# Power.net
KiCad netlist of a schematic drawn in Altium Designer
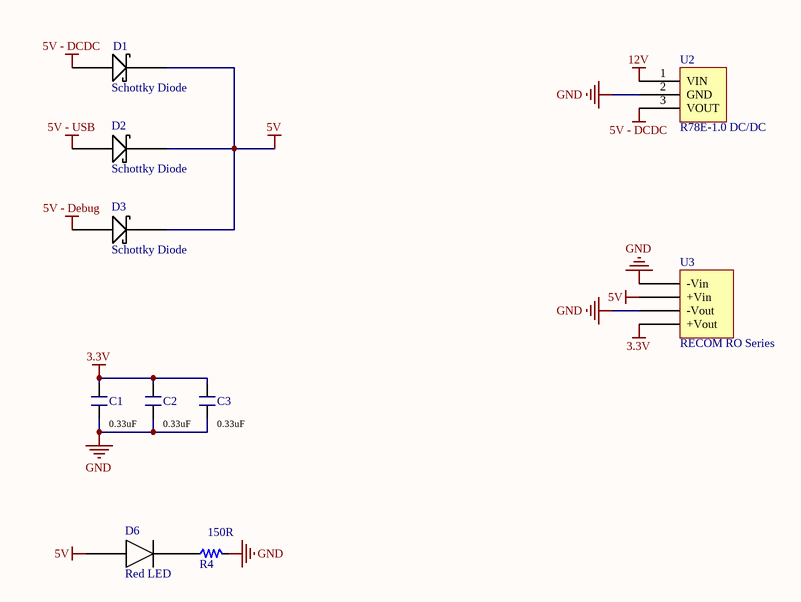
[diagram p0: Power.SchDoc]

(export (version "E")
  (design (tool "Eeschema 10.0.6"))
  (components
    (comp (ref "C1")
      (value "SCH_GENERIC_CAPACITOR_0603")
      (footprint "PCB_GENERIC_SMD_0603")
      (description "Generic SMD capacitor 0603")
      (fields (field (name "CAPACITANCE") "0.33uF"))
      (libsource (lib "Capacitors") (part "SCH_GENERIC_CAPACITOR_0603"))
    )
    (comp (ref "C2")
      (value "SCH_GENERIC_CAPACITOR_0603")
      (footprint "PCB_GENERIC_SMD_0603")
      (description "Generic SMD capacitor 0603")
      (fields (field (name "TOLERANCE") "*%") (field (name "CAPACITANCE") "0.33uF"))
      (libsource (lib "Capacitors") (part "SCH_GENERIC_CAPACITOR_0603"))
    )
    (comp (ref "C3")
      (value "SCH_GENERIC_CAPACITOR_0603")
      (footprint "PCB_GENERIC_SMD_0603")
      (description "Generic SMD capacitor 0603")
      (fields (field (name "TOLERANCE") "*%") (field (name "CAPACITANCE") "0.33uF"))
      (libsource (lib "Capacitors") (part "SCH_GENERIC_CAPACITOR_0603"))
    )
    (comp (ref "D1")
      (value "Schottky Diode")
      (footprint "ON Semi Schottky Diode - MBRM110LT1G")
      (libsource (lib "ON Semi Schottky Diode - MBRM110LT1G") (part "ON Semi Schottky Diode - MBRM110LT1G"))
    )
    (comp (ref "D2")
      (value "Schottky Diode")
      (footprint "ON Semi Schottky Diode - MBRM110LT1G")
      (libsource (lib "ON Semi Schottky Diode - MBRM110LT1G") (part "ON Semi Schottky Diode - MBRM110LT1G"))
    )
    (comp (ref "D3")
      (value "Schottky Diode")
      (footprint "ON Semi Schottky Diode - MBRM110LT1G")
      (libsource (lib "ON Semi Schottky Diode - MBRM110LT1G") (part "ON Semi Schottky Diode - MBRM110LT1G"))
    )
    (comp (ref "D6")
      (value "Red LED")
      (footprint "SMD_0603_LED")
      (libsource (lib "SMD_0603_LED") (part "SMD_0603_LED"))
    )
    (comp (ref "R4")
      (value "SCH_GENERIC_RESISTOR_0603")
      (footprint "PCB_GENERIC_SMD_0603")
      (description "Generic SMD resistor 0603")
      (fields (field (name "RESISTANCE") "150R"))
      (libsource (lib "SCH_GENERIC_RESISTOR_0603") (part "SCH_GENERIC_RESISTOR_0603"))
    )
    (comp (ref "U2")
      (value "R78E-1.0 DC/DC")
      (footprint "R78-1.0")
      (libsource (lib "R78E-1.0_DCDC_SCH") (part "R78E-1.0"))
    )
    (comp (ref "U3")
      (value "RECOM RO Series")
      (footprint "RECOM RO Series 1W DCDC")
      (libsource (lib "RECOM RO Series 1W DCDC") (part "RECOM RO Series DCDC Converter"))
    )
  )
  (nets
    (net (code "1") (name "3.3V") (class "Default")
      (node (ref "C1") (pin "2") (pinfunction "2_2") (pintype "passive"))
      (node (ref "C2") (pin "2") (pinfunction "2_2") (pintype "passive"))
      (node (ref "C3") (pin "2") (pinfunction "2_2") (pintype "passive"))
      (node (ref "U3") (pin "4") (pinfunction "+Vout_4") (pintype "passive"))
    )
    (net (code "2") (name "5V") (class "Default")
      (node (ref "D1") (pin "1") (pinfunction "1_1") (pintype "passive"))
      (node (ref "D2") (pin "1") (pinfunction "1_1") (pintype "passive"))
      (node (ref "D3") (pin "1") (pinfunction "1_1") (pintype "passive"))
      (node (ref "D6") (pin "1") (pinfunction "1_1") (pintype "passive"))
      (node (ref "U3") (pin "2") (pinfunction "+Vin_2") (pintype "passive"))
    )
    (net (code "3") (name "5V - DCDC") (class "Default")
      (node (ref "D1") (pin "2") (pinfunction "2_2") (pintype "passive"))
      (node (ref "U2") (pin "3") (pinfunction "VOUT_3") (pintype "passive"))
    )
    (net (code "4") (name "5V - Debug") (class "Default")
      (node (ref "D3") (pin "2") (pinfunction "2_2") (pintype "passive"))
    )
    (net (code "5") (name "5V - USB") (class "Default")
      (node (ref "D2") (pin "2") (pinfunction "2_2") (pintype "passive"))
    )
    (net (code "6") (name "12V") (class "Default")
      (node (ref "U2") (pin "1") (pinfunction "VIN_1") (pintype "passive"))
    )
    (net (code "7") (name "GND") (class "Default")
      (node (ref "C1") (pin "1") (pinfunction "1_1") (pintype "passive"))
      (node (ref "C2") (pin "1") (pinfunction "1_1") (pintype "passive"))
      (node (ref "C3") (pin "1") (pinfunction "1_1") (pintype "passive"))
      (node (ref "R4") (pin "2") (pinfunction "2_2") (pintype "passive"))
      (node (ref "U2") (pin "2") (pinfunction "GND_2") (pintype "passive"))
      (node (ref "U3") (pin "1") (pinfunction "-Vin_1") (pintype "passive"))
      (node (ref "U3") (pin "3") (pinfunction "-Vout_3") (pintype "passive"))
    )
    (net (code "8") (name "Net-(D6-Pad2)") (class "Default")
      (node (ref "D6") (pin "2") (pinfunction "2_2") (pintype "passive"))
      (node (ref "R4") (pin "1") (pinfunction "1_1") (pintype "passive"))
    )
  )
)
